# LCMeter-LCD4Bit-18F2550-CMP.net
KiCad netlist of a schematic drawn in EAGLE
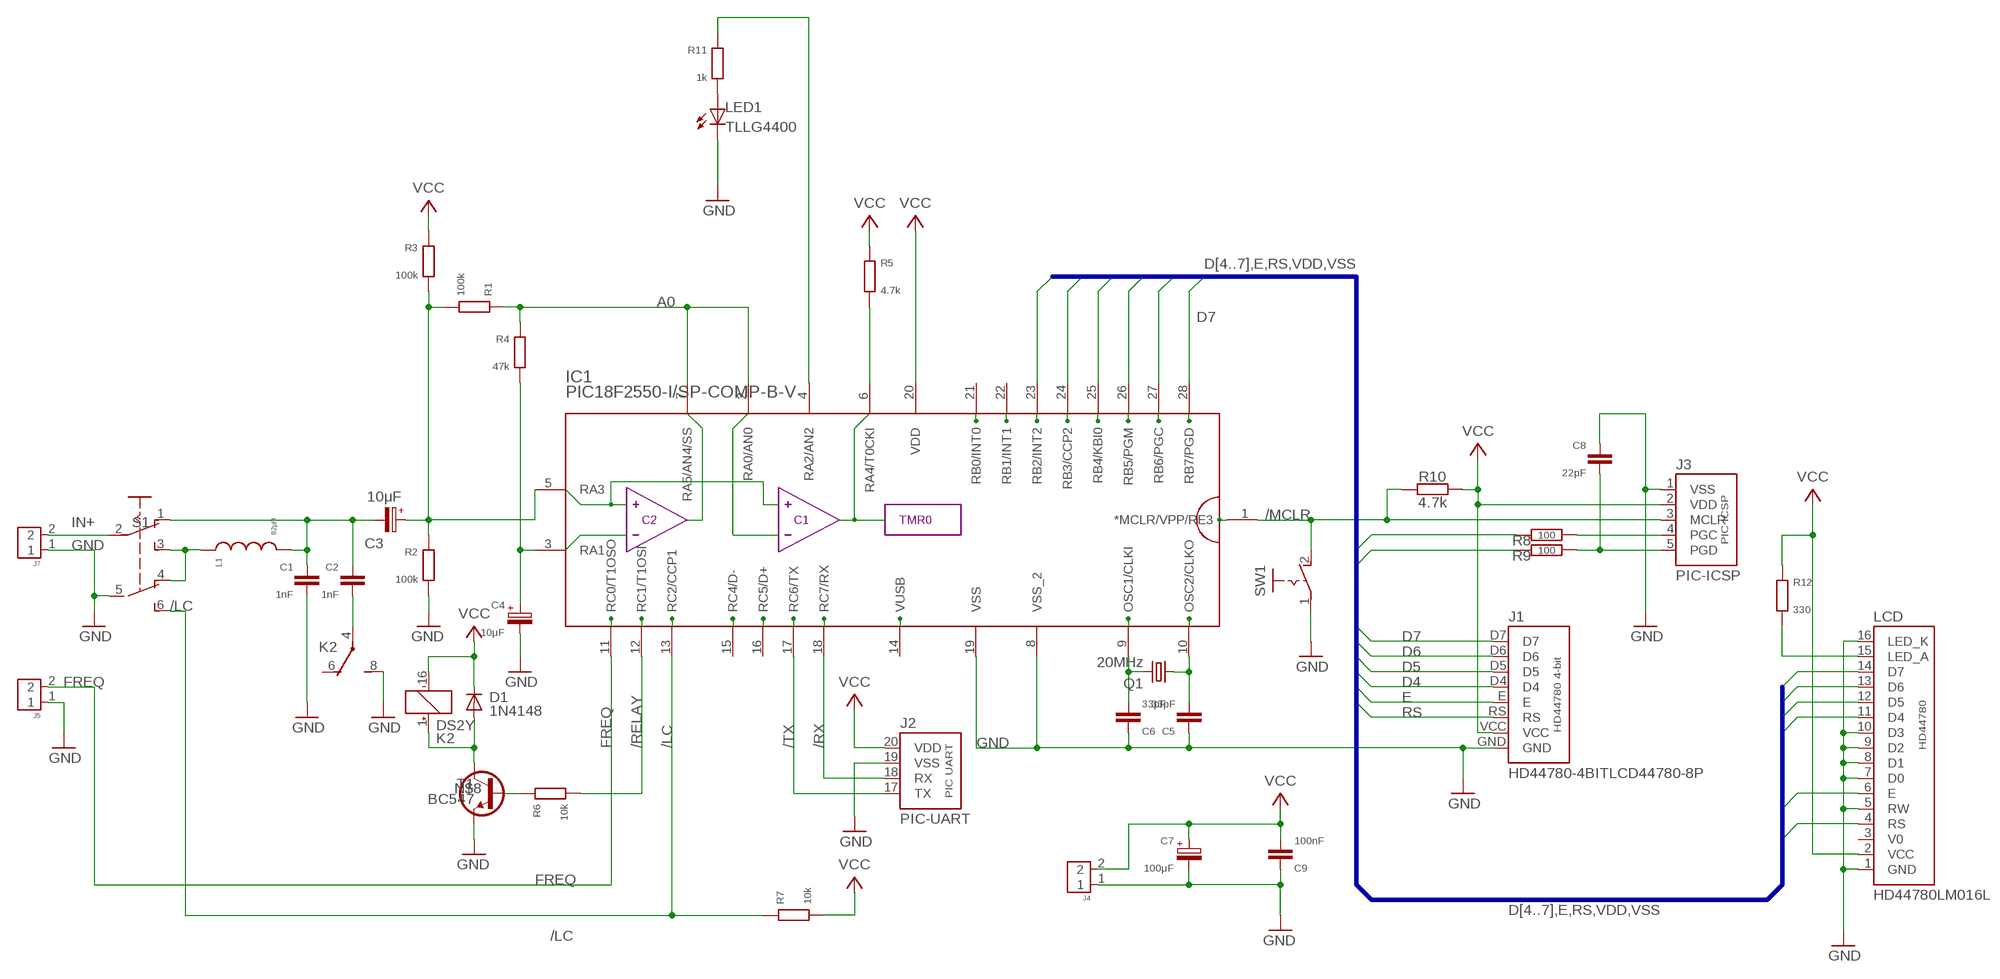
[diagram p0: schematic, sheet 1]

(export (version "E")
  (design (tool "Eeschema 10.0.6"))
  (components
    (comp (ref "C1")
      (value "1nF")
      (footprint "eagle-import:C050-025X060")
      (libsource (lib "eagle-import") (part "C025-025X060"))
    )
    (comp (ref "C2")
      (value "1nF")
      (footprint "eagle-import:C050-025X060")
      (libsource (lib "eagle-import") (part "C025-025X060"))
    )
    (comp (ref "C3")
      (value "10μF")
      (footprint "eagle-import:E2,5-4")
      (libsource (lib "eagle-import") (part "CPOLE2,5-4"))
    )
    (comp (ref "C4")
      (value "10μF")
      (footprint "eagle-import:E2,5-4")
      (libsource (lib "eagle-import") (part "CPOLE2,5-4"))
    )
    (comp (ref "C5")
      (value "33pF")
      (footprint "eagle-import:C025-020X036")
      (libsource (lib "eagle-import") (part "C025-020X036"))
    )
    (comp (ref "C6")
      (value "33pF")
      (footprint "eagle-import:C025-020X036")
      (libsource (lib "eagle-import") (part "C025-020X036"))
    )
    (comp (ref "C7")
      (value "100μF")
      (footprint "eagle-import:E2,5-5")
      (libsource (lib "eagle-import") (part "CPOLE2.5-5"))
    )
    (comp (ref "C8")
      (value "22pF")
      (footprint "eagle-import:C050-020X036")
      (libsource (lib "eagle-import") (part "C050-020X036"))
    )
    (comp (ref "C9")
      (value "100nF")
      (footprint "eagle-import:C025-020X036_V")
      (libsource (lib "eagle-import") (part "C025-020X036/V"))
    )
    (comp (ref "D1")
      (value "1N4148")
      (footprint "eagle-import:DO34-7")
      (libsource (lib "eagle-import") (part "1N414834-7"))
    )
    (comp (ref "IC1")
      (value "PIC18F2550-I/SP-COMP-B-V")
      (footprint "eagle-import:DIL28-3_V")
      (libsource (lib "eagle-import") (part "PIC18F2550-I/SP-COMP-B-V"))
    )
    (comp (ref "J1")
      (value "HD44780-4BITLCD44780-8P")
      (footprint "eagle-import:CONN-LCD44780")
      (libsource (lib "eagle-import") (part "HD44780-4BITLCD44780-8P"))
    )
    (comp (ref "J2")
      (value "PIC-UART")
      (footprint "eagle-import:PIC-UART")
      (libsource (lib "eagle-import") (part "PIC-UART"))
    )
    (comp (ref "J3")
      (value "PIC-ICSP")
      (footprint "eagle-import:PIC-ICSP")
      (libsource (lib "eagle-import") (part "PIC-ICSPICSP"))
    )
    (comp (ref "J4")
      (value "J4")
      (footprint "eagle-import:CONN-2P")
      (libsource (lib "eagle-import") (part "CONN-2P2P/H"))
    )
    (comp (ref "J5")
      (value "CONN-2P2P/V")
      (footprint "eagle-import:CONN-2P-V")
      (libsource (lib "eagle-import") (part "CONN-2P2P/V"))
    )
    (comp (ref "J7")
      (value "CONN-2P2P/V")
      (footprint "eagle-import:CONN-2P-V")
      (libsource (lib "eagle-import") (part "CONN-2P2P/V"))
    )
    (comp (ref "K2")
      (value "DS2Y")
      (footprint "eagle-import:DS2Y")
      (fields (field (name "MPN") "DS2Y-S-DC5V"))
      (libsource (lib "eagle-import") (part "DS2Y-S-DC5V"))
    )
    (comp (ref "L1")
      (value "82μH")
      (footprint "eagle-import:0207_10")
      (libsource (lib "eagle-import") (part "LAXIAL"))
    )
    (comp (ref "LCD")
      (value "HD44780LM016L")
      (footprint "eagle-import:LM016L-HD44780")
      (libsource (lib "eagle-import") (part "HD44780LM016L"))
    )
    (comp (ref "LED1")
      (value "TLLG4400")
      (footprint "eagle-import:LED3MM")
      (fields (field (name "MF") "VISHAY SEMICONDUCTOR"))
      (libsource (lib "eagle-import") (part "TLLG4400"))
    )
    (comp (ref "Q1")
      (value "20MHz")
      (footprint "eagle-import:HC49")
      (libsource (lib "eagle-import") (part "CRYSTALHC49"))
    )
    (comp (ref "R1")
      (value "100k")
      (footprint "eagle-import:0202_7")
      (libsource (lib "eagle-import") (part "R0202/7"))
    )
    (comp (ref "R2")
      (value "100k")
      (footprint "eagle-import:0202_7")
      (libsource (lib "eagle-import") (part "R0202/7"))
    )
    (comp (ref "R3")
      (value "100k")
      (footprint "eagle-import:0202_7")
      (libsource (lib "eagle-import") (part "R0202/7"))
    )
    (comp (ref "R4")
      (value "47k")
      (footprint "eagle-import:0202_7")
      (libsource (lib "eagle-import") (part "R0202/7"))
    )
    (comp (ref "R5")
      (value "4.7k")
      (footprint "eagle-import:0202_7")
      (libsource (lib "eagle-import") (part "R0202/7"))
    )
    (comp (ref "R6")
      (value "10k")
      (footprint "eagle-import:0202_7-V")
      (libsource (lib "eagle-import") (part "R0202/7-V"))
    )
    (comp (ref "R7")
      (value "10k")
      (footprint "eagle-import:0202_10-V")
      (libsource (lib "eagle-import") (part "R0202/10-V"))
    )
    (comp (ref "R8")
      (value "100")
      (footprint "eagle-import:0202_7-V")
      (libsource (lib "eagle-import") (part "R0202/7-V"))
    )
    (comp (ref "R9")
      (value "100")
      (footprint "eagle-import:0202_5-V")
      (libsource (lib "eagle-import") (part "R0202/5-V"))
    )
    (comp (ref "R10")
      (value "4.7k")
      (footprint "eagle-import:0202_7")
      (libsource (lib "eagle-import") (part "R0202/7"))
    )
    (comp (ref "R11")
      (value "1k")
      (footprint "eagle-import:0202_5-V")
      (libsource (lib "eagle-import") (part "R0202/5-V"))
    )
    (comp (ref "R12")
      (value "330")
      (footprint "eagle-import:0202_7")
      (libsource (lib "eagle-import") (part "R0202/7"))
    )
    (comp (ref "S1")
      (value "SL-SW-2P-2T")
      (footprint "eagle-import:SLSW-2P2T")
      (libsource (lib "eagle-import") (part "SL-SW-2P-2T"))
    )
    (comp (ref "SW1")
      (value "PB-1P-1T")
      (footprint "eagle-import:PB-1P1T")
      (libsource (lib "eagle-import") (part "PB-1P-1T"))
    )
    (comp (ref "T1")
      (value "BC547")
      (footprint "eagle-import:TO92-CBE-A")
      (libsource (lib "eagle-import") (part "BC547CBE-A"))
    )
  )
  (nets
    (net (code "3") (name "/A0") (class "Default")
      (node (ref "IC1") (pin "2") (pinfunction "RA0/AN0_2") (pintype "passive"))
      (node (ref "IC1") (pin "7") (pinfunction "RA5/AN4/SS_7") (pintype "passive"))
      (node (ref "R1") (pin "2") (pinfunction "2_2") (pintype "passive"))
      (node (ref "R4") (pin "2") (pinfunction "2_2") (pintype "passive"))
    )
    (net (code "4") (name "/D4") (class "Default")
      (node (ref "IC1") (pin "25") (pinfunction "RB4/KBI0_25") (pintype "passive"))
      (node (ref "J1") (pin "D4") (pinfunction "D4_D4") (pintype "passive"))
      (node (ref "LCD") (pin "11") (pinfunction "D4_11") (pintype "passive"))
    )
    (net (code "5") (name "/D5") (class "Default")
      (node (ref "IC1") (pin "26") (pinfunction "RB5/PGM_26") (pintype "passive"))
      (node (ref "J1") (pin "D5") (pinfunction "D5_D5") (pintype "passive"))
      (node (ref "LCD") (pin "12") (pinfunction "D5_12") (pintype "passive"))
    )
    (net (code "6") (name "/D6") (class "Default")
      (node (ref "IC1") (pin "27") (pinfunction "RB6/PGC_27") (pintype "passive"))
      (node (ref "J1") (pin "D6") (pinfunction "D6_D6") (pintype "passive"))
      (node (ref "LCD") (pin "13") (pinfunction "D6_13") (pintype "passive"))
      (node (ref "R8") (pin "2") (pinfunction "2_2") (pintype "passive"))
    )
    (net (code "7") (name "/D7") (class "Default")
      (node (ref "IC1") (pin "28") (pinfunction "RB7/PGD_28") (pintype "passive"))
      (node (ref "J1") (pin "D7") (pinfunction "D7_D7") (pintype "passive"))
      (node (ref "LCD") (pin "14") (pinfunction "D7_14") (pintype "passive"))
      (node (ref "R9") (pin "2") (pinfunction "2_2") (pintype "passive"))
    )
    (net (code "8") (name "/E") (class "Default")
      (node (ref "IC1") (pin "24") (pinfunction "RB3/CCP2_24") (pintype "passive"))
      (node (ref "J1") (pin "E") (pinfunction "E_E") (pintype "passive"))
      (node (ref "LCD") (pin "6") (pinfunction "E_6") (pintype "passive"))
    )
    (net (code "9") (name "/FREQ") (class "Default")
      (node (ref "IC1") (pin "11") (pinfunction "RC0/T1OSO_11") (pintype "passive"))
      (node (ref "J5") (pin "2") (pinfunction "2_2") (pintype "bidirectional"))
    )
    (net (code "10") (name "/IN+") (class "Default")
      (node (ref "J7") (pin "2") (pinfunction "2_2") (pintype "bidirectional"))
      (node (ref "S1") (pin "2") (pinfunction "P_2") (pintype "passive"))
    )
    (net (code "11") (name "/N$8") (class "Default")
      (node (ref "D1") (pin "A") (pinfunction "A_A") (pintype "passive"))
      (node (ref "K2") (pin "1") (pinfunction "+_1") (pintype "passive"))
      (node (ref "T1") (pin "C") (pinfunction "C_C") (pintype "passive"))
    )
    (net (code "12") (name "/RS") (class "Default")
      (node (ref "IC1") (pin "23") (pinfunction "RB2/INT2_23") (pintype "passive"))
      (node (ref "J1") (pin "RS") (pinfunction "RS_RS") (pintype "passive"))
      (node (ref "LCD") (pin "4") (pinfunction "RS_4") (pintype "passive"))
    )
    (net (code "14") (name "/{slash}LC") (class "Default")
      (node (ref "IC1") (pin "13") (pinfunction "RC2/CCP1_13") (pintype "passive"))
      (node (ref "R7") (pin "2") (pinfunction "2_2") (pintype "passive"))
      (node (ref "S1") (pin "6") (pinfunction "S1_6") (pintype "passive"))
    )
    (net (code "15") (name "/{slash}MCLR") (class "Default")
      (node (ref "IC1") (pin "1") (pinfunction "*MCLR/VPP/RE3_1") (pintype "passive"))
      (node (ref "J3") (pin "3") (pinfunction "MCLR_3") (pintype "passive"))
      (node (ref "R10") (pin "2") (pinfunction "2_2") (pintype "passive"))
      (node (ref "SW1") (pin "2") (pinfunction "S_2") (pintype "passive"))
    )
    (net (code "16") (name "/{slash}RELAY") (class "Default")
      (node (ref "IC1") (pin "12") (pinfunction "RC1/T1OSI_12") (pintype "passive"))
      (node (ref "R6") (pin "1") (pinfunction "1_1") (pintype "passive"))
    )
    (net (code "17") (name "/{slash}RX") (class "Default")
      (node (ref "IC1") (pin "18") (pinfunction "RC7/RX_18") (pintype "passive"))
      (node (ref "J2") (pin "18") (pinfunction "RX_18") (pintype "passive"))
    )
    (net (code "18") (name "/{slash}TX") (class "Default")
      (node (ref "IC1") (pin "17") (pinfunction "RC6/TX_17") (pintype "passive"))
      (node (ref "J2") (pin "17") (pinfunction "TX_17") (pintype "passive"))
    )
    (net (code "19") (name "GND") (class "Default")
      (node (ref "C1") (pin "2") (pinfunction "2_2") (pintype "passive"))
      (node (ref "C4") (pin "-") (pinfunction "-_-") (pintype "passive"))
      (node (ref "C5") (pin "1") (pinfunction "1_1") (pintype "passive"))
      (node (ref "C6") (pin "1") (pinfunction "1_1") (pintype "passive"))
      (node (ref "C7") (pin "-") (pinfunction "-_-") (pintype "passive"))
      (node (ref "C8") (pin "1") (pinfunction "1_1") (pintype "passive"))
      (node (ref "C9") (pin "1") (pinfunction "1_1") (pintype "passive"))
      (node (ref "IC1") (pin "19") (pinfunction "VSS_19") (pintype "passive"))
      (node (ref "IC1") (pin "8") (pinfunction "VSS_2_8") (pintype "passive"))
      (node (ref "J1") (pin "GND") (pinfunction "GND_GND") (pintype "passive"))
      (node (ref "J2") (pin "19") (pinfunction "VSS_19") (pintype "passive"))
      (node (ref "J3") (pin "1") (pinfunction "VSS_1") (pintype "passive"))
      (node (ref "J4") (pin "1") (pinfunction "1_1") (pintype "bidirectional"))
      (node (ref "J5") (pin "1") (pinfunction "1_1") (pintype "bidirectional"))
      (node (ref "J7") (pin "1") (pinfunction "1_1") (pintype "bidirectional"))
      (node (ref "K2") (pin "8") (pinfunction "S_8") (pintype "passive"))
      (node (ref "LCD") (pin "1") (pinfunction "GND_1") (pintype "passive"))
      (node (ref "LCD") (pin "10") (pinfunction "D3_10") (pintype "passive"))
      (node (ref "LCD") (pin "16") (pinfunction "LED_K_16") (pintype "passive"))
      (node (ref "LCD") (pin "5") (pinfunction "RW_5") (pintype "passive"))
      (node (ref "LCD") (pin "7") (pinfunction "D0_7") (pintype "passive"))
      (node (ref "LCD") (pin "8") (pinfunction "D1_8") (pintype "passive"))
      (node (ref "LCD") (pin "9") (pinfunction "D2_9") (pintype "passive"))
      (node (ref "LED1") (pin "K") (pinfunction "C_K") (pintype "passive"))
      (node (ref "R2") (pin "1") (pinfunction "1_1") (pintype "passive"))
      (node (ref "S1") (pin "5") (pinfunction "P1_5") (pintype "passive"))
      (node (ref "SW1") (pin "1") (pinfunction "P_1") (pintype "passive"))
      (node (ref "T1") (pin "E") (pinfunction "E_E") (pintype "passive"))
    )
    (net (code "20") (name "Net-(IC1-OSC1{slash}CLKI)") (class "Default")
      (node (ref "C6") (pin "2") (pinfunction "2_2") (pintype "passive"))
      (node (ref "IC1") (pin "9") (pinfunction "OSC1/CLKI_9") (pintype "passive"))
      (node (ref "Q1") (pin "2") (pinfunction "2_2") (pintype "passive"))
    )
    (net (code "21") (name "Net-(IC1-OSC2{slash}CLKO)") (class "Default")
      (node (ref "C5") (pin "2") (pinfunction "2_2") (pintype "passive"))
      (node (ref "IC1") (pin "10") (pinfunction "OSC2/CLKO_10") (pintype "passive"))
      (node (ref "Q1") (pin "1") (pinfunction "1_1") (pintype "passive"))
    )
    (net (code "22") (name "Net-(IC1-RA1)") (class "Default")
      (node (ref "C4") (pin "+") (pinfunction "+_+") (pintype "passive"))
      (node (ref "IC1") (pin "3") (pinfunction "RA1_3") (pintype "passive"))
      (node (ref "R4") (pin "1") (pinfunction "1_1") (pintype "passive"))
    )
    (net (code "23") (name "Net-(IC1-RA2{slash}AN2)") (class "Default")
      (node (ref "IC1") (pin "4") (pinfunction "RA2/AN2_4") (pintype "passive"))
      (node (ref "R11") (pin "2") (pinfunction "2_2") (pintype "passive"))
    )
    (net (code "24") (name "Net-(IC1-RA3)") (class "Default")
      (node (ref "C3") (pin "+") (pinfunction "+_+") (pintype "passive"))
      (node (ref "IC1") (pin "5") (pinfunction "RA3_5") (pintype "passive"))
      (node (ref "R1") (pin "1") (pinfunction "1_1") (pintype "passive"))
      (node (ref "R2") (pin "2") (pinfunction "2_2") (pintype "passive"))
      (node (ref "R3") (pin "1") (pinfunction "1_1") (pintype "passive"))
    )
    (net (code "25") (name "Net-(IC1-RA4{slash}T0CKI)") (class "Default")
      (node (ref "IC1") (pin "6") (pinfunction "RA4/T0CKI_6") (pintype "passive"))
      (node (ref "R5") (pin "1") (pinfunction "1_1") (pintype "passive"))
    )
    (net (code "26") (name "Net-(J3-PGC)") (class "Default")
      (node (ref "J3") (pin "4") (pinfunction "PGC_4") (pintype "passive"))
      (node (ref "R8") (pin "1") (pinfunction "1_1") (pintype "passive"))
    )
    (net (code "27") (name "Net-(J3-PGD)") (class "Default")
      (node (ref "C8") (pin "2") (pinfunction "2_2") (pintype "passive"))
      (node (ref "J3") (pin "5") (pinfunction "PGD_5") (pintype "passive"))
      (node (ref "R9") (pin "1") (pinfunction "1_1") (pintype "passive"))
    )
    (net (code "28") (name "Net-(K2B-P)") (class "Default")
      (node (ref "C2") (pin "2") (pinfunction "2_2") (pintype "passive"))
      (node (ref "K2") (pin "4") (pinfunction "P_4") (pintype "passive"))
    )
    (net (code "29") (name "Net-(LCD-LED_A)") (class "Default")
      (node (ref "LCD") (pin "15") (pinfunction "LED_A_15") (pintype "passive"))
      (node (ref "R12") (pin "1") (pinfunction "1_1") (pintype "passive"))
    )
    (net (code "30") (name "Net-(LED1-PadA)") (class "Default")
      (node (ref "LED1") (pin "A") (pinfunction "A_A") (pintype "passive"))
      (node (ref "R11") (pin "1") (pinfunction "1_1") (pintype "passive"))
    )
    (net (code "31") (name "Net-(R6-Pad2)") (class "Default")
      (node (ref "R6") (pin "2") (pinfunction "2_2") (pintype "passive"))
      (node (ref "T1") (pin "B") (pinfunction "B_B") (pintype "passive"))
    )
    (net (code "32") (name "Net-(S1-O)") (class "Default")
      (node (ref "C1") (pin "1") (pinfunction "1_1") (pintype "passive"))
      (node (ref "C2") (pin "1") (pinfunction "1_1") (pintype "passive"))
      (node (ref "C3") (pin "-") (pinfunction "-_-") (pintype "passive"))
      (node (ref "L1") (pin "2") (pinfunction "2_2") (pintype "passive"))
      (node (ref "S1") (pin "1") (pinfunction "O_1") (pintype "passive"))
    )
    (net (code "33") (name "Net-(S1-O1)") (class "Default")
      (node (ref "L1") (pin "1") (pinfunction "1_1") (pintype "passive"))
      (node (ref "S1") (pin "3") (pinfunction "S_3") (pintype "passive"))
      (node (ref "S1") (pin "4") (pinfunction "O1_4") (pintype "passive"))
    )
    (net (code "34") (name "VCC") (class "Default")
      (node (ref "C7") (pin "+") (pinfunction "+_+") (pintype "passive"))
      (node (ref "C9") (pin "2") (pinfunction "2_2") (pintype "passive"))
      (node (ref "D1") (pin "C") (pinfunction "C_C") (pintype "passive"))
      (node (ref "IC1") (pin "20") (pinfunction "VDD_20") (pintype "passive"))
      (node (ref "J1") (pin "VCC") (pinfunction "VCC_VCC") (pintype "passive"))
      (node (ref "J2") (pin "20") (pinfunction "VDD_20") (pintype "passive"))
      (node (ref "J3") (pin "2") (pinfunction "VDD_2") (pintype "passive"))
      (node (ref "J4") (pin "2") (pinfunction "2_2") (pintype "bidirectional"))
      (node (ref "K2") (pin "16") (pinfunction "-_16") (pintype "passive"))
      (node (ref "LCD") (pin "2") (pinfunction "VCC_2") (pintype "passive"))
      (node (ref "R10") (pin "1") (pinfunction "1_1") (pintype "passive"))
      (node (ref "R12") (pin "2") (pinfunction "2_2") (pintype "passive"))
      (node (ref "R3") (pin "2") (pinfunction "2_2") (pintype "passive"))
      (node (ref "R5") (pin "2") (pinfunction "2_2") (pintype "passive"))
      (node (ref "R7") (pin "1") (pinfunction "1_1") (pintype "passive"))
    )
    (net (code "35") (name "unconnected-(IC1-RB0{slash}INT0-Pad21)") (class "Default")
      (node (ref "IC1") (pin "21") (pinfunction "RB0/INT0_21") (pintype "passive"))
    )
    (net (code "36") (name "unconnected-(IC1-RB1{slash}INT1-Pad22)") (class "Default")
      (node (ref "IC1") (pin "22") (pinfunction "RB1/INT1_22") (pintype "passive"))
    )
    (net (code "37") (name "unconnected-(IC1-RC4{slash}D--Pad15)") (class "Default")
      (node (ref "IC1") (pin "15") (pinfunction "RC4/D-_15") (pintype "passive"))
    )
    (net (code "38") (name "unconnected-(IC1-RC5{slash}D+-Pad16)") (class "Default")
      (node (ref "IC1") (pin "16") (pinfunction "RC5/D+_16") (pintype "passive"))
    )
    (net (code "39") (name "unconnected-(IC1-VUSB-Pad14)") (class "Default")
      (node (ref "IC1") (pin "14") (pinfunction "VUSB_14") (pintype "passive"))
    )
    (net (code "40") (name "unconnected-(K2B-O-Pad6)") (class "Default")
      (node (ref "K2") (pin "6") (pinfunction "O_6") (pintype "passive"))
    )
    (net (code "41") (name "unconnected-(LCD-V0-Pad3)") (class "Default")
      (node (ref "LCD") (pin "3") (pinfunction "V0_3") (pintype "passive"))
    )
  )
)
